# MonoMixer.net
KiCad netlist of a schematic drawn in EAGLE
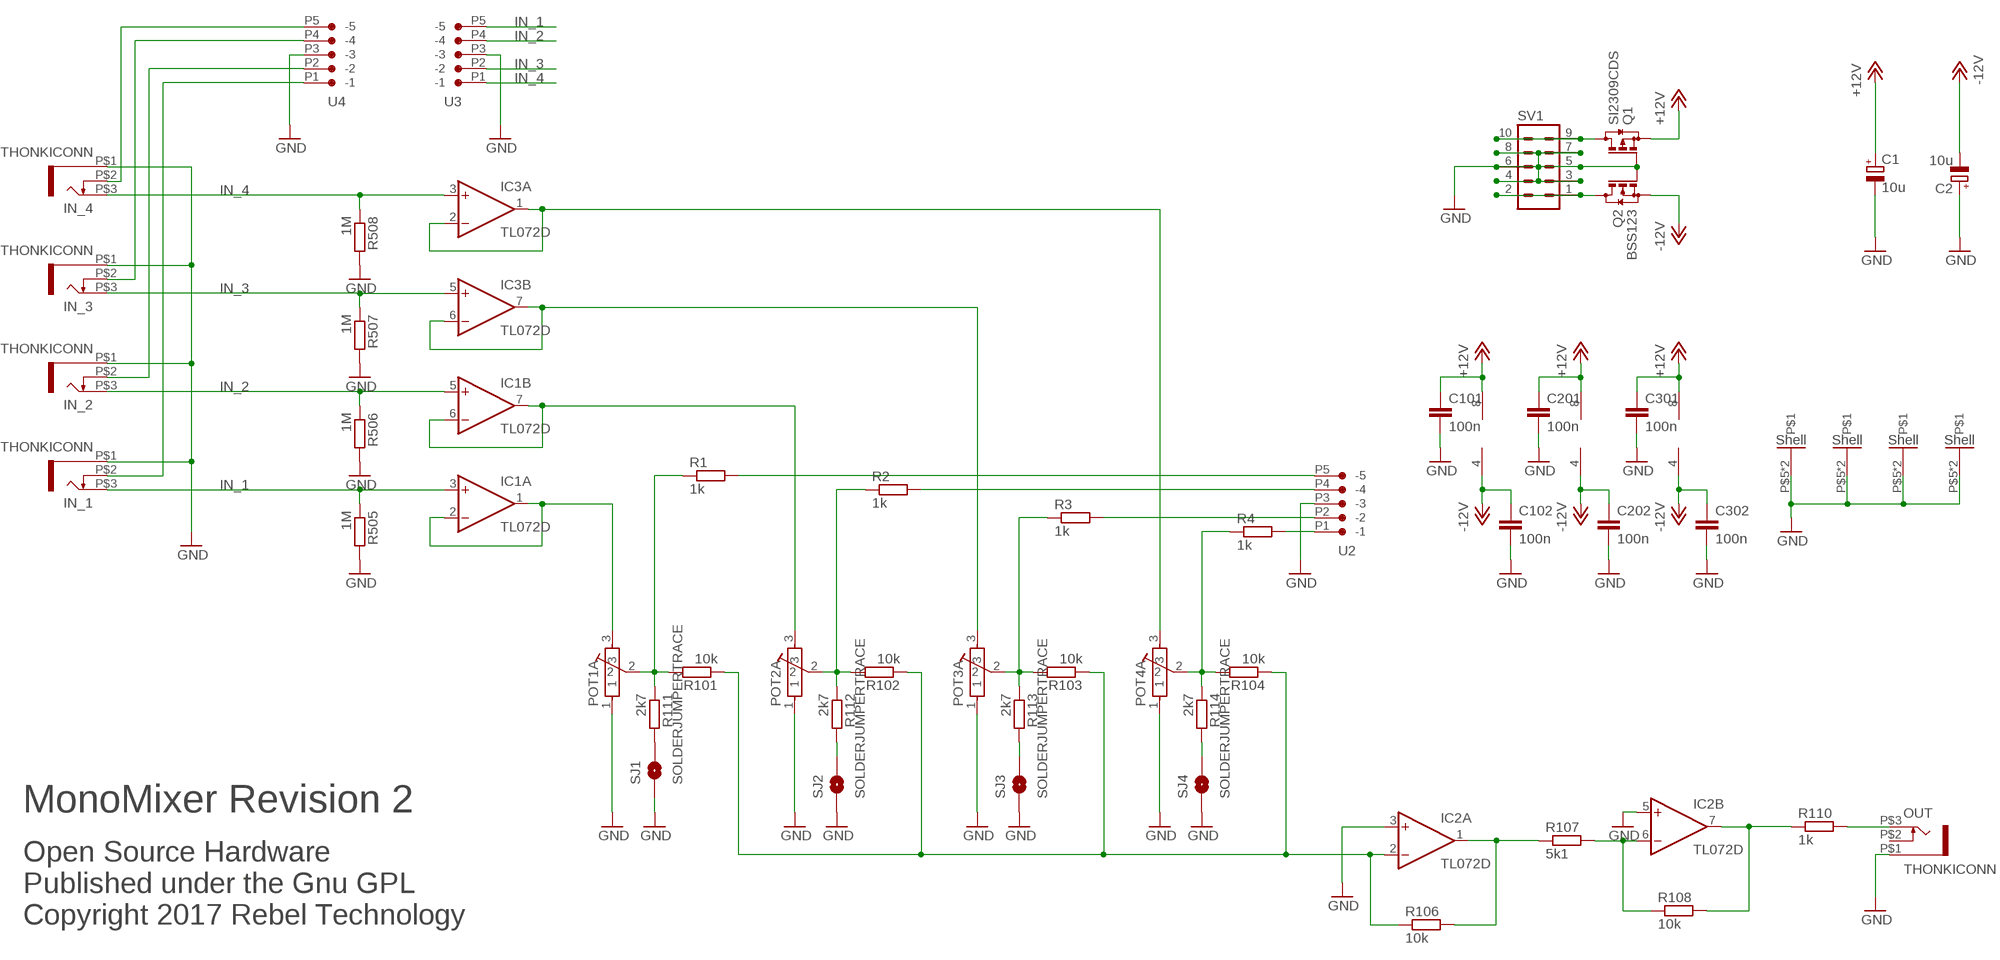
[diagram p0: schematic, sheet 1]

(export (version "E")
  (design (tool "Eeschema 10.0.6"))
  (components
    (comp (ref "C1")
      (value "10u")
      (footprint "eagle-import:153CLV-0505")
      (libsource (lib "eagle-import") (part "CPOL-EU153CLV-0505"))
    )
    (comp (ref "C2")
      (value "10u")
      (footprint "eagle-import:153CLV-0505")
      (libsource (lib "eagle-import") (part "CPOL-EU153CLV-0505"))
    )
    (comp (ref "C101")
      (value "100n")
      (footprint "eagle-import:C0603")
      (libsource (lib "eagle-import") (part "C-EUC0603"))
    )
    (comp (ref "C102")
      (value "100n")
      (footprint "eagle-import:C0603")
      (libsource (lib "eagle-import") (part "C-EUC0603"))
    )
    (comp (ref "C201")
      (value "100n")
      (footprint "eagle-import:C0603")
      (libsource (lib "eagle-import") (part "C-EUC0603"))
    )
    (comp (ref "C202")
      (value "100n")
      (footprint "eagle-import:C0603")
      (libsource (lib "eagle-import") (part "C-EUC0603"))
    )
    (comp (ref "C301")
      (value "100n")
      (footprint "eagle-import:C0603")
      (libsource (lib "eagle-import") (part "C-EUC0603"))
    )
    (comp (ref "C302")
      (value "100n")
      (footprint "eagle-import:C0603")
      (libsource (lib "eagle-import") (part "C-EUC0603"))
    )
    (comp (ref "IC1")
      (value "TL072D")
      (footprint "eagle-import:SO08")
      (libsource (lib "eagle-import") (part "TL072D"))
    )
    (comp (ref "IC2")
      (value "TL072D")
      (footprint "eagle-import:SO08")
      (libsource (lib "eagle-import") (part "TL072D"))
    )
    (comp (ref "IC3")
      (value "TL072D")
      (footprint "eagle-import:SO08")
      (libsource (lib "eagle-import") (part "TL072D"))
    )
    (comp (ref "IN_1")
      (value "THONKICONN")
      (footprint "eagle-import:THONKICONN")
      (libsource (lib "eagle-import") (part "THONKICONN"))
    )
    (comp (ref "IN_2")
      (value "THONKICONN")
      (footprint "eagle-import:THONKICONN")
      (libsource (lib "eagle-import") (part "THONKICONN"))
    )
    (comp (ref "IN_3")
      (value "THONKICONN")
      (footprint "eagle-import:THONKICONN")
      (libsource (lib "eagle-import") (part "THONKICONN"))
    )
    (comp (ref "IN_4")
      (value "THONKICONN")
      (footprint "eagle-import:THONKICONN")
      (libsource (lib "eagle-import") (part "THONKICONN"))
    )
    (comp (ref "OUT")
      (value "THONKICONN")
      (footprint "eagle-import:THONKICONN")
      (libsource (lib "eagle-import") (part "THONKICONN"))
    )
    (comp (ref "POT1A")
      (value "POT-ALPS-RK09L1140")
      (footprint "eagle-import:POT-ALPS-RK09L1140")
      (libsource (lib "eagle-import") (part "POT-ALPS-RK09L1140"))
    )
    (comp (ref "POT2A")
      (value "POT-ALPS-RK09L1140")
      (footprint "eagle-import:POT-ALPS-RK09L1140")
      (libsource (lib "eagle-import") (part "POT-ALPS-RK09L1140"))
    )
    (comp (ref "POT3A")
      (value "POT-ALPS-RK09L1140")
      (footprint "eagle-import:POT-ALPS-RK09L1140")
      (libsource (lib "eagle-import") (part "POT-ALPS-RK09L1140"))
    )
    (comp (ref "POT4A")
      (value "POT-ALPS-RK09L1140")
      (footprint "eagle-import:POT-ALPS-RK09L1140")
      (libsource (lib "eagle-import") (part "POT-ALPS-RK09L1140"))
    )
    (comp (ref "Q1")
      (value "SI2309CDS")
      (footprint "eagle-import:SOT23")
      (libsource (lib "eagle-import") (part "BSS84"))
    )
    (comp (ref "Q2")
      (value "BSS123")
      (footprint "eagle-import:SOT23")
      (libsource (lib "eagle-import") (part "BSS123"))
    )
    (comp (ref "R1")
      (value "1k")
      (footprint "eagle-import:R0603")
      (libsource (lib "eagle-import") (part "R-EU_R0603"))
    )
    (comp (ref "R2")
      (value "1k")
      (footprint "eagle-import:R0603")
      (libsource (lib "eagle-import") (part "R-EU_R0603"))
    )
    (comp (ref "R3")
      (value "1k")
      (footprint "eagle-import:R0603")
      (libsource (lib "eagle-import") (part "R-EU_R0603"))
    )
    (comp (ref "R4")
      (value "1k")
      (footprint "eagle-import:R0603")
      (libsource (lib "eagle-import") (part "R-EU_R0603"))
    )
    (comp (ref "R101")
      (value "10k")
      (footprint "eagle-import:R0603")
      (libsource (lib "eagle-import") (part "R-EU_R0603"))
    )
    (comp (ref "R102")
      (value "10k")
      (footprint "eagle-import:R0603")
      (libsource (lib "eagle-import") (part "R-EU_R0603"))
    )
    (comp (ref "R103")
      (value "10k")
      (footprint "eagle-import:R0603")
      (libsource (lib "eagle-import") (part "R-EU_R0603"))
    )
    (comp (ref "R104")
      (value "10k")
      (footprint "eagle-import:R0603")
      (libsource (lib "eagle-import") (part "R-EU_R0603"))
    )
    (comp (ref "R106")
      (value "10k")
      (footprint "eagle-import:R0603")
      (libsource (lib "eagle-import") (part "R-EU_R0603"))
    )
    (comp (ref "R107")
      (value "5k1")
      (footprint "eagle-import:R0603")
      (libsource (lib "eagle-import") (part "R-EU_R0603"))
    )
    (comp (ref "R108")
      (value "10k")
      (footprint "eagle-import:R0603")
      (libsource (lib "eagle-import") (part "R-EU_R0603"))
    )
    (comp (ref "R110")
      (value "1k")
      (footprint "eagle-import:R0603")
      (libsource (lib "eagle-import") (part "R-EU_R0603"))
    )
    (comp (ref "R111")
      (value "2k7")
      (footprint "eagle-import:R0603")
      (libsource (lib "eagle-import") (part "R-EU_R0603"))
    )
    (comp (ref "R112")
      (value "2k7")
      (footprint "eagle-import:R0603")
      (libsource (lib "eagle-import") (part "R-EU_R0603"))
    )
    (comp (ref "R113")
      (value "2k7")
      (footprint "eagle-import:R0603")
      (libsource (lib "eagle-import") (part "R-EU_R0603"))
    )
    (comp (ref "R114")
      (value "2k7")
      (footprint "eagle-import:R0603")
      (libsource (lib "eagle-import") (part "R-EU_R0603"))
    )
    (comp (ref "R505")
      (value "1M")
      (footprint "eagle-import:R0603")
      (libsource (lib "eagle-import") (part "R-EU_R0603"))
    )
    (comp (ref "R506")
      (value "1M")
      (footprint "eagle-import:R0603")
      (libsource (lib "eagle-import") (part "R-EU_R0603"))
    )
    (comp (ref "R507")
      (value "1M")
      (footprint "eagle-import:R0603")
      (libsource (lib "eagle-import") (part "R-EU_R0603"))
    )
    (comp (ref "R508")
      (value "1M")
      (footprint "eagle-import:R0603")
      (libsource (lib "eagle-import") (part "R-EU_R0603"))
    )
    (comp (ref "SJ1")
      (value "SOLDERJUMPERTRACE")
      (footprint "eagle-import:SJ_2S-TRACE")
      (libsource (lib "eagle-import") (part "SOLDERJUMPERTRACE"))
    )
    (comp (ref "SJ2")
      (value "SOLDERJUMPERTRACE")
      (footprint "eagle-import:SJ_2S-TRACE")
      (libsource (lib "eagle-import") (part "SOLDERJUMPERTRACE"))
    )
    (comp (ref "SJ3")
      (value "SOLDERJUMPERTRACE")
      (footprint "eagle-import:SJ_2S-TRACE")
      (libsource (lib "eagle-import") (part "SOLDERJUMPERTRACE"))
    )
    (comp (ref "SJ4")
      (value "SOLDERJUMPERTRACE")
      (footprint "eagle-import:SJ_2S-TRACE")
      (libsource (lib "eagle-import") (part "SOLDERJUMPERTRACE"))
    )
    (comp (ref "SV1")
      (value "MA05-2")
      (footprint "eagle-import:MA05-2")
      (libsource (lib "eagle-import") (part "MA05-2"))
    )
    (comp (ref "U2")
      (value "CON-JST_PH_5W")
      (footprint "eagle-import:CON-JST_PH_5W")
      (libsource (lib "eagle-import") (part "CON-JST_PH_5W"))
    )
    (comp (ref "U3")
      (value "CON-JST_PH_5W")
      (footprint "eagle-import:CON-JST_PH_5W")
      (libsource (lib "eagle-import") (part "CON-JST_PH_5W"))
    )
    (comp (ref "U4")
      (value "CON-JST_PH_5W")
      (footprint "eagle-import:CON-JST_PH_5W")
      (libsource (lib "eagle-import") (part "CON-JST_PH_5W"))
    )
  )
  (nets
    (net (code "1") (name "+12V") (class "Default")
      (node (ref "C1") (pin "+") (pinfunction "+_+") (pintype "passive"))
      (node (ref "C101") (pin "1") (pinfunction "1_1") (pintype "passive"))
      (node (ref "C201") (pin "1") (pinfunction "1_1") (pintype "passive"))
      (node (ref "C301") (pin "1") (pinfunction "1_1") (pintype "passive"))
      (node (ref "IC1") (pin "8") (pinfunction "V+_8") (pintype "power_in"))
      (node (ref "IC2") (pin "8") (pinfunction "V+_8") (pintype "power_in"))
      (node (ref "IC3") (pin "8") (pinfunction "V+_8") (pintype "power_in"))
      (node (ref "Q1") (pin "2") (pinfunction "S_2") (pintype "passive"))
    )
    (net (code "2") (name "-12V") (class "Default")
      (node (ref "C102") (pin "1") (pinfunction "1_1") (pintype "passive"))
      (node (ref "C2") (pin "-") (pinfunction "-_-") (pintype "passive"))
      (node (ref "C202") (pin "1") (pinfunction "1_1") (pintype "passive"))
      (node (ref "C302") (pin "1") (pinfunction "1_1") (pintype "passive"))
      (node (ref "IC1") (pin "4") (pinfunction "V-_4") (pintype "power_in"))
      (node (ref "IC2") (pin "4") (pinfunction "V-_4") (pintype "power_in"))
      (node (ref "IC3") (pin "4") (pinfunction "V-_4") (pintype "power_in"))
      (node (ref "Q2") (pin "2") (pinfunction "S_2") (pintype "passive"))
    )
    (net (code "3") (name "/IN_1") (class "Default")
      (node (ref "IC1") (pin "3") (pinfunction "+IN_3") (pintype "input"))
      (node (ref "IN_1") (pin "P$3") (pinfunction "3_P$3") (pintype "passive"))
      (node (ref "R505") (pin "1") (pinfunction "1_1") (pintype "passive"))
      (node (ref "U3") (pin "P5") (pinfunction "-5_P5") (pintype "bidirectional"))
    )
    (net (code "4") (name "/IN_2") (class "Default")
      (node (ref "IC1") (pin "5") (pinfunction "+IN_5") (pintype "input"))
      (node (ref "IN_2") (pin "P$3") (pinfunction "3_P$3") (pintype "passive"))
      (node (ref "R506") (pin "1") (pinfunction "1_1") (pintype "passive"))
      (node (ref "U3") (pin "P4") (pinfunction "-4_P4") (pintype "bidirectional"))
    )
    (net (code "5") (name "/IN_3") (class "Default")
      (node (ref "IC3") (pin "5") (pinfunction "+IN_5") (pintype "input"))
      (node (ref "IN_3") (pin "P$3") (pinfunction "3_P$3") (pintype "passive"))
      (node (ref "R507") (pin "1") (pinfunction "1_1") (pintype "passive"))
      (node (ref "U3") (pin "P2") (pinfunction "-2_P2") (pintype "bidirectional"))
    )
    (net (code "6") (name "/IN_4") (class "Default")
      (node (ref "IC3") (pin "3") (pinfunction "+IN_3") (pintype "input"))
      (node (ref "IN_4") (pin "P$3") (pinfunction "3_P$3") (pintype "passive"))
      (node (ref "R508") (pin "1") (pinfunction "1_1") (pintype "passive"))
      (node (ref "U3") (pin "P1") (pinfunction "-1_P1") (pintype "bidirectional"))
    )
    (net (code "7") (name "GND") (class "Default")
      (node (ref "C1") (pin "-") (pinfunction "-_-") (pintype "passive"))
      (node (ref "C101") (pin "2") (pinfunction "2_2") (pintype "passive"))
      (node (ref "C102") (pin "2") (pinfunction "2_2") (pintype "passive"))
      (node (ref "C2") (pin "+") (pinfunction "+_+") (pintype "passive"))
      (node (ref "C201") (pin "2") (pinfunction "2_2") (pintype "passive"))
      (node (ref "C202") (pin "2") (pinfunction "2_2") (pintype "passive"))
      (node (ref "C301") (pin "2") (pinfunction "2_2") (pintype "passive"))
      (node (ref "C302") (pin "2") (pinfunction "2_2") (pintype "passive"))
      (node (ref "IC2") (pin "3") (pinfunction "+IN_3") (pintype "input"))
      (node (ref "IC2") (pin "5") (pinfunction "+IN_5") (pintype "input"))
      (node (ref "IN_1") (pin "P$1") (pinfunction "5_P$1") (pintype "passive"))
      (node (ref "IN_2") (pin "P$1") (pinfunction "5_P$1") (pintype "passive"))
      (node (ref "IN_3") (pin "P$1") (pinfunction "5_P$1") (pintype "passive"))
      (node (ref "IN_4") (pin "P$1") (pinfunction "5_P$1") (pintype "passive"))
      (node (ref "OUT") (pin "P$1") (pinfunction "5_P$1") (pintype "passive"))
      (node (ref "POT1A") (pin "1") (pinfunction "1_1") (pintype "bidirectional"))
      (node (ref "POT1A") (pin "P$5") (pinfunction "P$1_P$5") (pintype "bidirectional"))
      (node (ref "POT1A") (pin "P$6") (pinfunction "P$1_P$6") (pintype "bidirectional"))
      (node (ref "POT2A") (pin "1") (pinfunction "1_1") (pintype "bidirectional"))
      (node (ref "POT2A") (pin "P$5") (pinfunction "P$1_P$5") (pintype "bidirectional"))
      (node (ref "POT2A") (pin "P$6") (pinfunction "P$1_P$6") (pintype "bidirectional"))
      (node (ref "POT3A") (pin "1") (pinfunction "1_1") (pintype "bidirectional"))
      (node (ref "POT3A") (pin "P$5") (pinfunction "P$1_P$5") (pintype "bidirectional"))
      (node (ref "POT3A") (pin "P$6") (pinfunction "P$1_P$6") (pintype "bidirectional"))
      (node (ref "POT4A") (pin "1") (pinfunction "1_1") (pintype "bidirectional"))
      (node (ref "POT4A") (pin "P$5") (pinfunction "P$1_P$5") (pintype "bidirectional"))
      (node (ref "POT4A") (pin "P$6") (pinfunction "P$1_P$6") (pintype "bidirectional"))
      (node (ref "Q1") (pin "1") (pinfunction "G_1") (pintype "passive"))
      (node (ref "Q2") (pin "1") (pinfunction "G_1") (pintype "passive"))
      (node (ref "R505") (pin "2") (pinfunction "2_2") (pintype "passive"))
      (node (ref "R506") (pin "2") (pinfunction "2_2") (pintype "passive"))
      (node (ref "R507") (pin "2") (pinfunction "2_2") (pintype "passive"))
      (node (ref "R508") (pin "2") (pinfunction "2_2") (pintype "passive"))
      (node (ref "SJ1") (pin "1") (pinfunction "1_1") (pintype "passive"))
      (node (ref "SJ2") (pin "1") (pinfunction "1_1") (pintype "passive"))
      (node (ref "SJ3") (pin "1") (pinfunction "1_1") (pintype "passive"))
      (node (ref "SJ4") (pin "1") (pinfunction "1_1") (pintype "passive"))
      (node (ref "SV1") (pin "3") (pinfunction "3_3") (pintype "passive"))
      (node (ref "SV1") (pin "4") (pinfunction "4_4") (pintype "passive"))
      (node (ref "SV1") (pin "5") (pinfunction "5_5") (pintype "passive"))
      (node (ref "SV1") (pin "6") (pinfunction "6_6") (pintype "passive"))
      (node (ref "SV1") (pin "7") (pinfunction "7_7") (pintype "passive"))
      (node (ref "SV1") (pin "8") (pinfunction "8_8") (pintype "passive"))
      (node (ref "U2") (pin "P3") (pinfunction "-3_P3") (pintype "bidirectional"))
      (node (ref "U3") (pin "P3") (pinfunction "-3_P3") (pintype "bidirectional"))
      (node (ref "U4") (pin "P3") (pinfunction "-3_P3") (pintype "bidirectional"))
    )
    (net (code "8") (name "Net-(IC1A--IN)") (class "Default")
      (node (ref "IC1") (pin "1") (pinfunction "OUT_1") (pintype "output"))
      (node (ref "IC1") (pin "2") (pinfunction "-IN_2") (pintype "input"))
      (node (ref "POT1A") (pin "3") (pinfunction "3_3") (pintype "bidirectional"))
    )
    (net (code "9") (name "Net-(IC1B--IN)") (class "Default")
      (node (ref "IC1") (pin "6") (pinfunction "-IN_6") (pintype "input"))
      (node (ref "IC1") (pin "7") (pinfunction "OUT_7") (pintype "output"))
      (node (ref "POT2A") (pin "3") (pinfunction "3_3") (pintype "bidirectional"))
    )
    (net (code "10") (name "Net-(IC2A--IN)") (class "Default")
      (node (ref "IC2") (pin "2") (pinfunction "-IN_2") (pintype "input"))
      (node (ref "R101") (pin "1") (pinfunction "1_1") (pintype "passive"))
      (node (ref "R102") (pin "1") (pinfunction "1_1") (pintype "passive"))
      (node (ref "R103") (pin "1") (pinfunction "1_1") (pintype "passive"))
      (node (ref "R104") (pin "1") (pinfunction "1_1") (pintype "passive"))
      (node (ref "R106") (pin "1") (pinfunction "1_1") (pintype "passive"))
    )
    (net (code "11") (name "Net-(IC2A-OUT)") (class "Default")
      (node (ref "IC2") (pin "1") (pinfunction "OUT_1") (pintype "output"))
      (node (ref "R106") (pin "2") (pinfunction "2_2") (pintype "passive"))
      (node (ref "R107") (pin "1") (pinfunction "1_1") (pintype "passive"))
    )
    (net (code "12") (name "Net-(IC2B--IN)") (class "Default")
      (node (ref "IC2") (pin "6") (pinfunction "-IN_6") (pintype "input"))
      (node (ref "R107") (pin "2") (pinfunction "2_2") (pintype "passive"))
      (node (ref "R108") (pin "1") (pinfunction "1_1") (pintype "passive"))
    )
    (net (code "13") (name "Net-(IC2B-OUT)") (class "Default")
      (node (ref "IC2") (pin "7") (pinfunction "OUT_7") (pintype "output"))
      (node (ref "R108") (pin "2") (pinfunction "2_2") (pintype "passive"))
      (node (ref "R110") (pin "1") (pinfunction "1_1") (pintype "passive"))
    )
    (net (code "14") (name "Net-(IC3A--IN)") (class "Default")
      (node (ref "IC3") (pin "1") (pinfunction "OUT_1") (pintype "output"))
      (node (ref "IC3") (pin "2") (pinfunction "-IN_2") (pintype "input"))
      (node (ref "POT4A") (pin "3") (pinfunction "3_3") (pintype "bidirectional"))
    )
    (net (code "15") (name "Net-(IC3B--IN)") (class "Default")
      (node (ref "IC3") (pin "6") (pinfunction "-IN_6") (pintype "input"))
      (node (ref "IC3") (pin "7") (pinfunction "OUT_7") (pintype "output"))
      (node (ref "POT3A") (pin "3") (pinfunction "3_3") (pintype "bidirectional"))
    )
    (net (code "16") (name "Net-(IN_1-4)") (class "Default")
      (node (ref "IN_1") (pin "P$2") (pinfunction "4_P$2") (pintype "passive"))
      (node (ref "U4") (pin "P1") (pinfunction "-1_P1") (pintype "bidirectional"))
    )
    (net (code "17") (name "Net-(IN_2-4)") (class "Default")
      (node (ref "IN_2") (pin "P$2") (pinfunction "4_P$2") (pintype "passive"))
      (node (ref "U4") (pin "P2") (pinfunction "-2_P2") (pintype "bidirectional"))
    )
    (net (code "18") (name "Net-(IN_3-4)") (class "Default")
      (node (ref "IN_3") (pin "P$2") (pinfunction "4_P$2") (pintype "passive"))
      (node (ref "U4") (pin "P4") (pinfunction "-4_P4") (pintype "bidirectional"))
    )
    (net (code "19") (name "Net-(IN_4-4)") (class "Default")
      (node (ref "IN_4") (pin "P$2") (pinfunction "4_P$2") (pintype "passive"))
      (node (ref "U4") (pin "P5") (pinfunction "-5_P5") (pintype "bidirectional"))
    )
    (net (code "20") (name "Net-(OUT-3)") (class "Default")
      (node (ref "OUT") (pin "P$3") (pinfunction "3_P$3") (pintype "passive"))
      (node (ref "R110") (pin "2") (pinfunction "2_2") (pintype "passive"))
    )
    (net (code "21") (name "Net-(POT1A-Pad2)") (class "Default")
      (node (ref "POT1A") (pin "2") (pinfunction "2_2") (pintype "bidirectional"))
      (node (ref "R1") (pin "1") (pinfunction "1_1") (pintype "passive"))
      (node (ref "R101") (pin "2") (pinfunction "2_2") (pintype "passive"))
      (node (ref "R111") (pin "1") (pinfunction "1_1") (pintype "passive"))
    )
    (net (code "22") (name "Net-(POT2A-Pad2)") (class "Default")
      (node (ref "POT2A") (pin "2") (pinfunction "2_2") (pintype "bidirectional"))
      (node (ref "R102") (pin "2") (pinfunction "2_2") (pintype "passive"))
      (node (ref "R112") (pin "1") (pinfunction "1_1") (pintype "passive"))
      (node (ref "R2") (pin "1") (pinfunction "1_1") (pintype "passive"))
    )
    (net (code "23") (name "Net-(POT3A-Pad2)") (class "Default")
      (node (ref "POT3A") (pin "2") (pinfunction "2_2") (pintype "bidirectional"))
      (node (ref "R103") (pin "2") (pinfunction "2_2") (pintype "passive"))
      (node (ref "R113") (pin "1") (pinfunction "1_1") (pintype "passive"))
      (node (ref "R3") (pin "1") (pinfunction "1_1") (pintype "passive"))
    )
    (net (code "24") (name "Net-(POT4A-Pad2)") (class "Default")
      (node (ref "POT4A") (pin "2") (pinfunction "2_2") (pintype "bidirectional"))
      (node (ref "R104") (pin "2") (pinfunction "2_2") (pintype "passive"))
      (node (ref "R114") (pin "1") (pinfunction "1_1") (pintype "passive"))
      (node (ref "R4") (pin "1") (pinfunction "1_1") (pintype "passive"))
    )
    (net (code "25") (name "Net-(Q1-D)") (class "Default")
      (node (ref "Q1") (pin "3") (pinfunction "D_3") (pintype "passive"))
      (node (ref "SV1") (pin "10") (pinfunction "10_10") (pintype "passive"))
      (node (ref "SV1") (pin "9") (pinfunction "9_9") (pintype "passive"))
    )
    (net (code "26") (name "Net-(Q2-D)") (class "Default")
      (node (ref "Q2") (pin "3") (pinfunction "D_3") (pintype "passive"))
      (node (ref "SV1") (pin "1") (pinfunction "1_1") (pintype "passive"))
      (node (ref "SV1") (pin "2") (pinfunction "2_2") (pintype "passive"))
    )
    (net (code "27") (name "Net-(R111-Pad2)") (class "Default")
      (node (ref "R111") (pin "2") (pinfunction "2_2") (pintype "passive"))
      (node (ref "SJ1") (pin "2") (pinfunction "2_2") (pintype "passive"))
    )
    (net (code "28") (name "Net-(R112-Pad2)") (class "Default")
      (node (ref "R112") (pin "2") (pinfunction "2_2") (pintype "passive"))
      (node (ref "SJ2") (pin "2") (pinfunction "2_2") (pintype "passive"))
    )
    (net (code "29") (name "Net-(R113-Pad2)") (class "Default")
      (node (ref "R113") (pin "2") (pinfunction "2_2") (pintype "passive"))
      (node (ref "SJ3") (pin "2") (pinfunction "2_2") (pintype "passive"))
    )
    (net (code "30") (name "Net-(R114-Pad2)") (class "Default")
      (node (ref "R114") (pin "2") (pinfunction "2_2") (pintype "passive"))
      (node (ref "SJ4") (pin "2") (pinfunction "2_2") (pintype "passive"))
    )
    (net (code "31") (name "Net-(U2--1)") (class "Default")
      (node (ref "R4") (pin "2") (pinfunction "2_2") (pintype "passive"))
      (node (ref "U2") (pin "P1") (pinfunction "-1_P1") (pintype "bidirectional"))
    )
    (net (code "32") (name "Net-(U2--2)") (class "Default")
      (node (ref "R3") (pin "2") (pinfunction "2_2") (pintype "passive"))
      (node (ref "U2") (pin "P2") (pinfunction "-2_P2") (pintype "bidirectional"))
    )
    (net (code "33") (name "Net-(U2--4)") (class "Default")
      (node (ref "R2") (pin "2") (pinfunction "2_2") (pintype "passive"))
      (node (ref "U2") (pin "P4") (pinfunction "-4_P4") (pintype "bidirectional"))
    )
    (net (code "34") (name "Net-(U2--5)") (class "Default")
      (node (ref "R1") (pin "2") (pinfunction "2_2") (pintype "passive"))
      (node (ref "U2") (pin "P5") (pinfunction "-5_P5") (pintype "bidirectional"))
    )
    (net (code "35") (name "unconnected-(OUT-4-PadP$2)") (class "Default")
      (node (ref "OUT") (pin "P$2") (pinfunction "4_P$2") (pintype "passive"))
    )
  )
)
